# LED_Indicator.net
KiCad netlist of a schematic drawn in Altium Designer
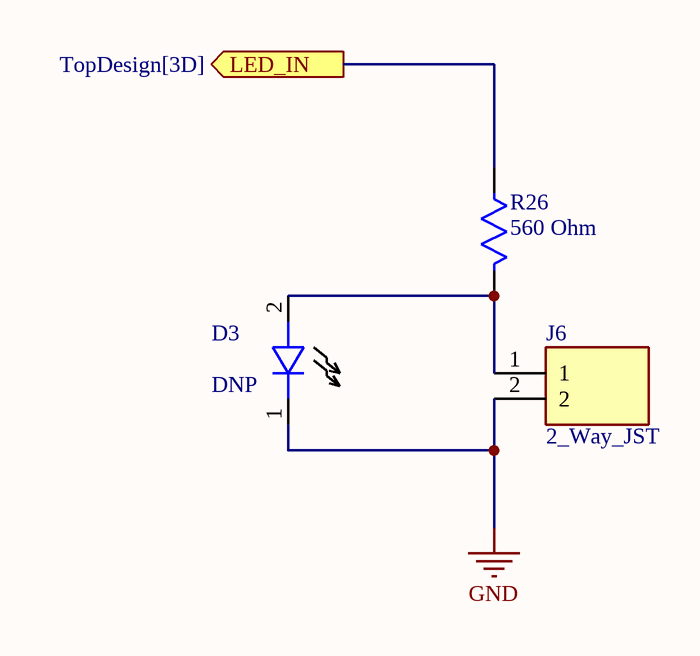
[diagram p0: LED_Indicator.SchDoc]

(export (version "E")
  (design (tool "Eeschema 10.0.6"))
  (components
    (comp (ref "D3")
      (value "DNP")
      (footprint "LED SMD 0603")
      (description "SMD LED")
      (libsource (lib "Aptinex_discrete") (part "LED SMD"))
    )
    (comp (ref "J6")
      (value "2_Way_JST")
      (footprint "2_Way_JST_Connector")
      (description "Connector Header Through Hole 2 position 0.098 (2.50mm)")
      (fields (field (name "MF") "JST Sales") (field (name "MP") "B2B-XH-A(LF)(SN)"))
      (libsource (lib "Aptinex_connectors") (part "2_Way_JST_Connector"))
    )
    (comp (ref "R26")
      (value "560 Ohm")
      (footprint "Res_0603")
      (description "SMD Resistor")
      (fields (field (name "MP") "RC0805FR-07330RL") (field (name "MF") "Yageo"))
      (libsource (lib "Aptinex_discrete") (part "Res smd"))
    )
  )
  (nets
    (net (code "1") (name "/LED_IN") (class "Default")
      (node (ref "R26") (pin "2") (pinfunction "2_2") (pintype "passive"))
    )
    (net (code "2") (name "GND") (class "Default")
      (node (ref "D3") (pin "1") (pinfunction "1_1") (pintype "passive"))
      (node (ref "J6") (pin "2") (pinfunction "2_2") (pintype "passive"))
    )
    (net (code "3") (name "Net-(D3-Pad2)") (class "Default")
      (node (ref "D3") (pin "2") (pinfunction "2_2") (pintype "passive"))
      (node (ref "J6") (pin "1") (pinfunction "1_1") (pintype "passive"))
      (node (ref "R26") (pin "1") (pinfunction "1_1") (pintype "passive"))
    )
  )
)
